# RH024_1.net
KiCad netlist of a schematic drawn in EAGLE
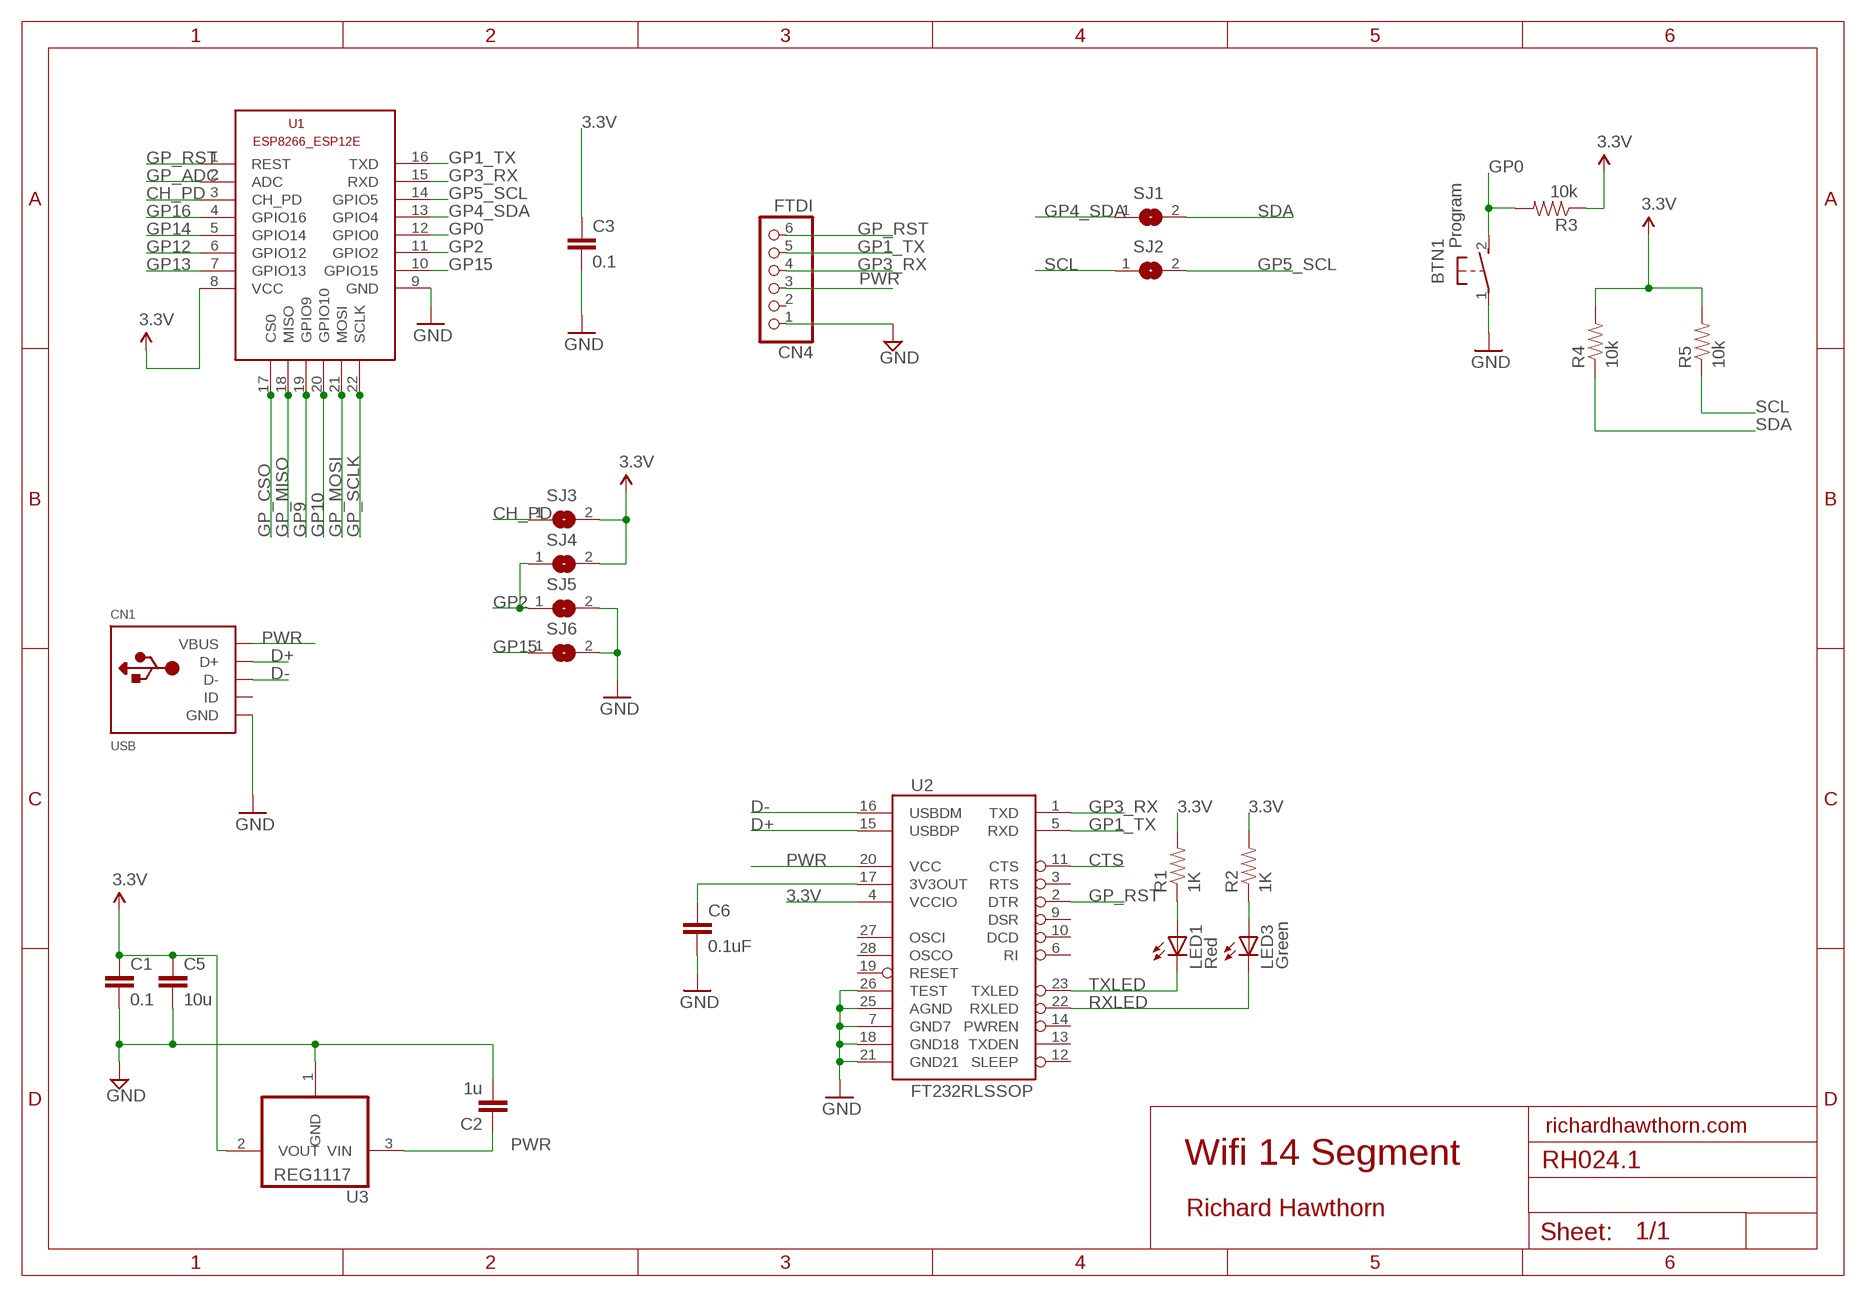
[diagram p0: schematic, sheet 1, part 1 of 2]
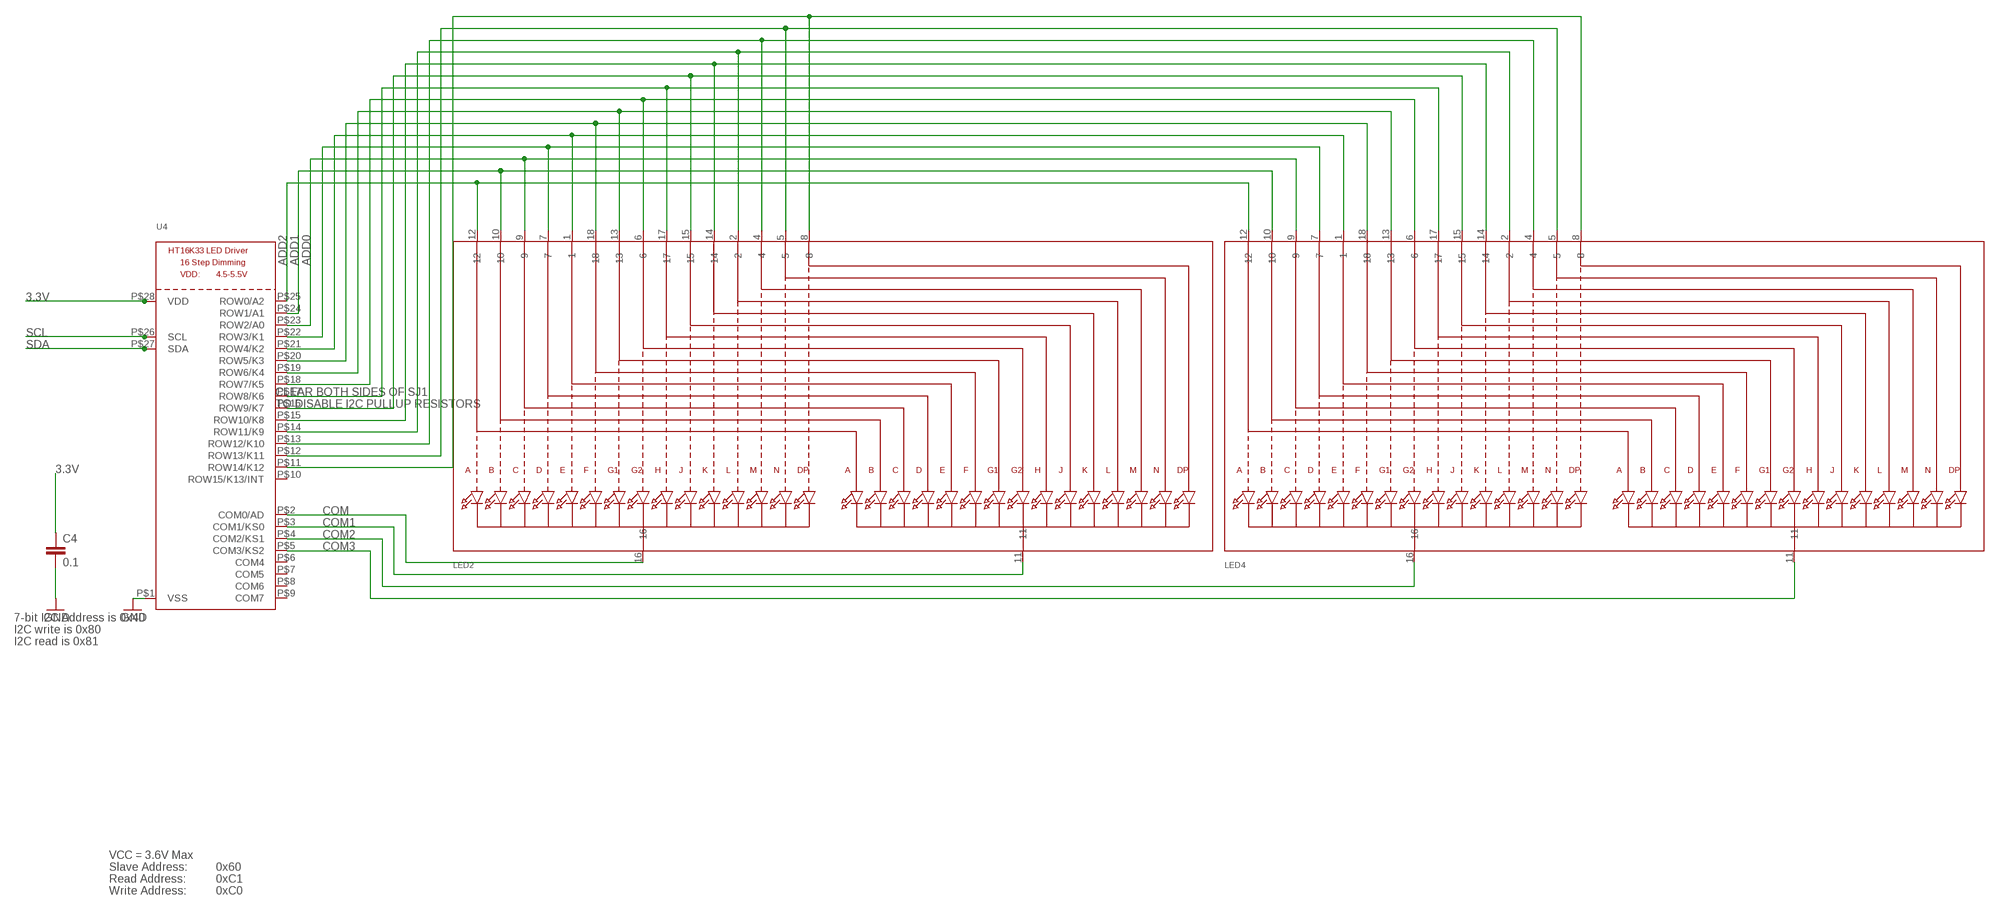
[diagram p1: schematic, sheet 1, part 2 of 2]

(export (version "E")
  (design (tool "Eeschema 10.0.6"))
  (components
    (comp (ref "BTN1")
      (value "Program")
      (footprint "eagle-import:DTS-3")
      (libsource (lib "eagle-import") (part "DTS-3"))
    )
    (comp (ref "C1")
      (value "0.1")
      (footprint "eagle-import:0603-CAP")
      (libsource (lib "eagle-import") (part "CAP0603-CAP"))
    )
    (comp (ref "C2")
      (value "1u")
      (footprint "eagle-import:0603-CAP")
      (libsource (lib "eagle-import") (part "CAP0603-CAP"))
    )
    (comp (ref "C3")
      (value "0.1")
      (footprint "eagle-import:0603-CAP")
      (libsource (lib "eagle-import") (part "CAP0603-CAP"))
    )
    (comp (ref "C4")
      (value "0.1")
      (footprint "eagle-import:0603-CAP")
      (libsource (lib "eagle-import") (part "CAP0603-CAP"))
    )
    (comp (ref "C5")
      (value "10u")
      (footprint "eagle-import:0805-CAP")
      (libsource (lib "eagle-import") (part "CAP0805-CAP"))
    )
    (comp (ref "C6")
      (value "0.1uF")
      (footprint "eagle-import:0402-CAP")
      (libsource (lib "eagle-import") (part "SparkFun_CAP0402-CAP"))
    )
    (comp (ref "CN1")
      (value "USB")
      (footprint "eagle-import:USB-MINIB")
      (libsource (lib "eagle-import") (part "USBMINIB"))
    )
    (comp (ref "CN4")
      (value "FTDI")
      (footprint "eagle-import:1X06")
      (libsource (lib "eagle-import") (part "PINHD-1X6"))
    )
    (comp (ref "LED1")
      (value "Red")
      (footprint "eagle-import:LED-0603")
      (libsource (lib "eagle-import") (part "LED0603"))
    )
    (comp (ref "LED2")
      (value "DISP_SEGMENT_STARBURST_DUAL_COMMONCATHODE")
      (footprint "eagle-import:SEGMENT_STARTBUST_DUAL_KWA-541CBB")
      (libsource (lib "eagle-import") (part "DISP_SEGMENT_STARBURST_DUAL_COMMONCATHODE"))
    )
    (comp (ref "LED3")
      (value "Green")
      (footprint "eagle-import:LED-0603")
      (libsource (lib "eagle-import") (part "LED0603"))
    )
    (comp (ref "LED4")
      (value "DISP_SEGMENT_STARBURST_DUAL_COMMONCATHODE")
      (footprint "eagle-import:SEGMENT_STARTBUST_DUAL_KWA-541CBB")
      (libsource (lib "eagle-import") (part "DISP_SEGMENT_STARBURST_DUAL_COMMONCATHODE"))
    )
    (comp (ref "R1")
      (value "1K")
      (footprint "eagle-import:0402-RES")
      (libsource (lib "eagle-import") (part "RESISTOR0402-RES"))
    )
    (comp (ref "R2")
      (value "1K")
      (footprint "eagle-import:0402-RES")
      (libsource (lib "eagle-import") (part "RESISTOR0402-RES"))
    )
    (comp (ref "R3")
      (value "10k")
      (footprint "eagle-import:0805")
      (libsource (lib "eagle-import") (part "RESISTOR0805-RES"))
    )
    (comp (ref "R4")
      (value "10k")
      (footprint "eagle-import:0805")
      (libsource (lib "eagle-import") (part "RESISTOR0805-RES"))
    )
    (comp (ref "R5")
      (value "10k")
      (footprint "eagle-import:0805")
      (libsource (lib "eagle-import") (part "RESISTOR0805-RES"))
    )
    (comp (ref "SJ1") (value "SJ") (footprint "eagle-import:SJ") (libsource (lib "eagle-import") (part "SJ")))
    (comp (ref "SJ2") (value "SJ") (footprint "eagle-import:SJ") (libsource (lib "eagle-import") (part "SJ")))
    (comp (ref "SJ3") (value "SJ") (footprint "eagle-import:SJ") (libsource (lib "eagle-import") (part "SJ")))
    (comp (ref "SJ4") (value "SJ") (footprint "eagle-import:SJ") (libsource (lib "eagle-import") (part "SJ")))
    (comp (ref "SJ5") (value "SJ") (footprint "eagle-import:SJ") (libsource (lib "eagle-import") (part "SJ")))
    (comp (ref "SJ6") (value "SJ") (footprint "eagle-import:SJ") (libsource (lib "eagle-import") (part "SJ")))
    (comp (ref "U1")
      (value "ESP8266-12EESP8266-ESP12E")
      (footprint "eagle-import:ESP8266-ESP12E")
      (libsource (lib "eagle-import") (part "ESP8266-12EESP8266-ESP12E"))
    )
    (comp (ref "U2")
      (value "FT232RLSSOP")
      (footprint "eagle-import:SSOP28DB")
      (libsource (lib "eagle-import") (part "FT232RLSSOP"))
    )
    (comp (ref "U3")
      (value "REG1117")
      (footprint "eagle-import:SOT223")
      (libsource (lib "eagle-import") (part "REG1117"))
    )
    (comp (ref "U4")
      (value "HT16K33_SOP28")
      (footprint "eagle-import:SOP28_300MIL")
      (libsource (lib "eagle-import") (part "HT16K33_SOP28"))
    )
  )
  (nets
    (net (code "1") (name "/ADD0") (class "Default")
      (node (ref "LED2") (pin "9") (pinfunction "9_9") (pintype "bidirectional"))
      (node (ref "LED4") (pin "9") (pinfunction "9_9") (pintype "bidirectional"))
      (node (ref "U4") (pin "P$23") (pinfunction "ROW2/A0_P$23") (pintype "bidirectional"))
    )
    (net (code "2") (name "/ADD1") (class "Default")
      (node (ref "LED2") (pin "10") (pinfunction "10_10") (pintype "bidirectional"))
      (node (ref "LED4") (pin "10") (pinfunction "10_10") (pintype "bidirectional"))
      (node (ref "U4") (pin "P$24") (pinfunction "ROW1/A1_P$24") (pintype "bidirectional"))
    )
    (net (code "3") (name "/ADD2") (class "Default")
      (node (ref "LED2") (pin "12") (pinfunction "12_12") (pintype "bidirectional"))
      (node (ref "LED4") (pin "12") (pinfunction "12_12") (pintype "bidirectional"))
      (node (ref "U4") (pin "P$25") (pinfunction "ROW0/A2_P$25") (pintype "bidirectional"))
    )
    (net (code "4") (name "/CH_PD") (class "Default")
      (node (ref "SJ3") (pin "1") (pinfunction "1_1") (pintype "passive"))
      (node (ref "U1") (pin "3") (pinfunction "CH_PD_3") (pintype "bidirectional"))
    )
    (net (code "5") (name "/COM") (class "Default")
      (node (ref "LED2") (pin "16") (pinfunction "16_16") (pintype "bidirectional"))
      (node (ref "U4") (pin "P$2") (pinfunction "COM0/AD_P$2") (pintype "bidirectional"))
    )
    (net (code "6") (name "/COM1") (class "Default")
      (node (ref "LED2") (pin "11") (pinfunction "11_11") (pintype "bidirectional"))
      (node (ref "U4") (pin "P$3") (pinfunction "COM1/KS0_P$3") (pintype "bidirectional"))
    )
    (net (code "7") (name "/COM2") (class "Default")
      (node (ref "LED4") (pin "16") (pinfunction "16_16") (pintype "bidirectional"))
      (node (ref "U4") (pin "P$4") (pinfunction "COM2/KS1_P$4") (pintype "bidirectional"))
    )
    (net (code "8") (name "/COM3") (class "Default")
      (node (ref "LED4") (pin "11") (pinfunction "11_11") (pintype "bidirectional"))
      (node (ref "U4") (pin "P$5") (pinfunction "COM3/KS2_P$5") (pintype "bidirectional"))
    )
    (net (code "9") (name "/CTS") (class "Default")
      (node (ref "U2") (pin "11") (pinfunction "CTS_11") (pintype "input"))
    )
    (net (code "10") (name "/D+") (class "Default")
      (node (ref "CN1") (pin "D+") (pinfunction "D+_D+") (pintype "bidirectional"))
      (node (ref "U2") (pin "15") (pinfunction "USBDP_15") (pintype "bidirectional"))
    )
    (net (code "11") (name "/D-") (class "Default")
      (node (ref "CN1") (pin "D-") (pinfunction "D-_D-") (pintype "bidirectional"))
      (node (ref "U2") (pin "16") (pinfunction "USBDM_16") (pintype "bidirectional"))
    )
    (net (code "12") (name "/GP0") (class "Default")
      (node (ref "BTN1") (pin "2") (pinfunction "2_2") (pintype "passive"))
      (node (ref "R3") (pin "2") (pinfunction "2_2") (pintype "passive"))
      (node (ref "U1") (pin "12") (pinfunction "GPIO0_12") (pintype "bidirectional"))
    )
    (net (code "13") (name "/GP1_TX") (class "Default")
      (node (ref "CN4") (pin "5") (pinfunction "5_5") (pintype "passive"))
      (node (ref "U1") (pin "16") (pinfunction "TXD_16") (pintype "bidirectional"))
      (node (ref "U2") (pin "5") (pinfunction "RXD_5") (pintype "input"))
    )
    (net (code "14") (name "/GP2") (class "Default")
      (node (ref "SJ4") (pin "1") (pinfunction "1_1") (pintype "passive"))
      (node (ref "SJ5") (pin "1") (pinfunction "1_1") (pintype "passive"))
      (node (ref "U1") (pin "11") (pinfunction "GPIO2_11") (pintype "bidirectional"))
    )
    (net (code "15") (name "/GP3_RX") (class "Default")
      (node (ref "CN4") (pin "4") (pinfunction "4_4") (pintype "passive"))
      (node (ref "U1") (pin "15") (pinfunction "RXD_15") (pintype "bidirectional"))
      (node (ref "U2") (pin "1") (pinfunction "TXD_1") (pintype "output"))
    )
    (net (code "16") (name "/GP4_SDA") (class "Default")
      (node (ref "SJ1") (pin "1") (pinfunction "1_1") (pintype "passive"))
      (node (ref "U1") (pin "13") (pinfunction "GPIO4_13") (pintype "bidirectional"))
    )
    (net (code "17") (name "/GP5_SCL") (class "Default")
      (node (ref "SJ2") (pin "2") (pinfunction "2_2") (pintype "passive"))
      (node (ref "U1") (pin "14") (pinfunction "GPIO5_14") (pintype "bidirectional"))
    )
    (net (code "18") (name "/GP9") (class "Default")
      (node (ref "U1") (pin "19") (pinfunction "GPIO9_19") (pintype "bidirectional"))
    )
    (net (code "19") (name "/GP10") (class "Default")
      (node (ref "U1") (pin "20") (pinfunction "GPIO10_20") (pintype "bidirectional"))
    )
    (net (code "20") (name "/GP12") (class "Default")
      (node (ref "U1") (pin "6") (pinfunction "GPIO12_6") (pintype "bidirectional"))
    )
    (net (code "21") (name "/GP13") (class "Default")
      (node (ref "U1") (pin "7") (pinfunction "GPIO13_7") (pintype "bidirectional"))
    )
    (net (code "22") (name "/GP14") (class "Default")
      (node (ref "U1") (pin "5") (pinfunction "GPIO14_5") (pintype "bidirectional"))
    )
    (net (code "23") (name "/GP15") (class "Default")
      (node (ref "SJ6") (pin "1") (pinfunction "1_1") (pintype "passive"))
      (node (ref "U1") (pin "10") (pinfunction "GPIO15_10") (pintype "bidirectional"))
    )
    (net (code "24") (name "/GP16") (class "Default")
      (node (ref "U1") (pin "4") (pinfunction "GPIO16_4") (pintype "bidirectional"))
    )
    (net (code "25") (name "/GP_ADC") (class "Default")
      (node (ref "U1") (pin "2") (pinfunction "ADC_2") (pintype "bidirectional"))
    )
    (net (code "26") (name "/GP_CSO") (class "Default")
      (node (ref "U1") (pin "17") (pinfunction "CS0_17") (pintype "bidirectional"))
    )
    (net (code "27") (name "/GP_MISO") (class "Default")
      (node (ref "U1") (pin "18") (pinfunction "MISO_18") (pintype "bidirectional"))
    )
    (net (code "28") (name "/GP_MOSI") (class "Default")
      (node (ref "U1") (pin "21") (pinfunction "MOSI_21") (pintype "bidirectional"))
    )
    (net (code "29") (name "/GP_RST") (class "Default")
      (node (ref "CN4") (pin "6") (pinfunction "6_6") (pintype "passive"))
      (node (ref "U1") (pin "1") (pinfunction "REST_1") (pintype "bidirectional"))
      (node (ref "U2") (pin "2") (pinfunction "DTR_2") (pintype "output"))
    )
    (net (code "30") (name "/GP_SCLK") (class "Default")
      (node (ref "U1") (pin "22") (pinfunction "SCLK_22") (pintype "bidirectional"))
    )
    (net (code "31") (name "/PWR") (class "Default")
      (node (ref "C2") (pin "1") (pinfunction "1_1") (pintype "passive"))
      (node (ref "CN1") (pin "VBUS") (pinfunction "VBUS_VBUS") (pintype "power_in"))
      (node (ref "CN4") (pin "3") (pinfunction "3_3") (pintype "passive"))
      (node (ref "U2") (pin "20") (pinfunction "VCC_20") (pintype "power_in"))
      (node (ref "U3") (pin "3") (pinfunction "VIN_3") (pintype "input"))
    )
    (net (code "32") (name "/RXLED") (class "Default")
      (node (ref "LED3") (pin "C") (pinfunction "C_C") (pintype "passive"))
      (node (ref "U2") (pin "22") (pinfunction "RXLED_22") (pintype "input"))
    )
    (net (code "33") (name "/SCL") (class "Default")
      (node (ref "R5") (pin "1") (pinfunction "1_1") (pintype "passive"))
      (node (ref "SJ2") (pin "1") (pinfunction "1_1") (pintype "passive"))
      (node (ref "U4") (pin "P$26") (pinfunction "SCL_P$26") (pintype "bidirectional"))
    )
    (net (code "34") (name "/SDA") (class "Default")
      (node (ref "R4") (pin "1") (pinfunction "1_1") (pintype "passive"))
      (node (ref "SJ1") (pin "2") (pinfunction "2_2") (pintype "passive"))
      (node (ref "U4") (pin "P$27") (pinfunction "SDA_P$27") (pintype "bidirectional"))
    )
    (net (code "35") (name "/TXLED") (class "Default")
      (node (ref "LED1") (pin "C") (pinfunction "C_C") (pintype "passive"))
      (node (ref "U2") (pin "23") (pinfunction "TXLED_23") (pintype "input"))
    )
    (net (code "36") (name "3.3V") (class "Default")
      (node (ref "C1") (pin "1") (pinfunction "1_1") (pintype "passive"))
      (node (ref "C3") (pin "1") (pinfunction "1_1") (pintype "passive"))
      (node (ref "C4") (pin "1") (pinfunction "1_1") (pintype "passive"))
      (node (ref "C5") (pin "1") (pinfunction "1_1") (pintype "passive"))
      (node (ref "R1") (pin "2") (pinfunction "2_2") (pintype "passive"))
      (node (ref "R2") (pin "2") (pinfunction "2_2") (pintype "passive"))
      (node (ref "R3") (pin "1") (pinfunction "1_1") (pintype "passive"))
      (node (ref "R4") (pin "2") (pinfunction "2_2") (pintype "passive"))
      (node (ref "R5") (pin "2") (pinfunction "2_2") (pintype "passive"))
      (node (ref "SJ3") (pin "2") (pinfunction "2_2") (pintype "passive"))
      (node (ref "SJ4") (pin "2") (pinfunction "2_2") (pintype "passive"))
      (node (ref "U1") (pin "8") (pinfunction "VCC_8") (pintype "bidirectional"))
      (node (ref "U2") (pin "4") (pinfunction "VCCIO_4") (pintype "power_in"))
      (node (ref "U3") (pin "2") (pinfunction "VOUT_2") (pintype "output"))
      (node (ref "U4") (pin "P$28") (pinfunction "VDD_P$28") (pintype "bidirectional"))
    )
    (net (code "37") (name "GND") (class "Default")
      (node (ref "BTN1") (pin "1") (pinfunction "1_1") (pintype "passive"))
      (node (ref "C1") (pin "2") (pinfunction "2_2") (pintype "passive"))
      (node (ref "C2") (pin "2") (pinfunction "2_2") (pintype "passive"))
      (node (ref "C3") (pin "2") (pinfunction "2_2") (pintype "passive"))
      (node (ref "C4") (pin "2") (pinfunction "2_2") (pintype "passive"))
      (node (ref "C5") (pin "2") (pinfunction "2_2") (pintype "passive"))
      (node (ref "C6") (pin "2") (pinfunction "2_2") (pintype "passive"))
      (node (ref "CN1") (pin "GND") (pinfunction "GND_GND") (pintype "power_in"))
      (node (ref "CN4") (pin "1") (pinfunction "1_1") (pintype "passive"))
      (node (ref "SJ5") (pin "2") (pinfunction "2_2") (pintype "passive"))
      (node (ref "SJ6") (pin "2") (pinfunction "2_2") (pintype "passive"))
      (node (ref "U1") (pin "9") (pinfunction "GND_9") (pintype "bidirectional"))
      (node (ref "U2") (pin "18") (pinfunction "GND18_18") (pintype "power_in"))
      (node (ref "U2") (pin "21") (pinfunction "GND21_21") (pintype "power_in"))
      (node (ref "U2") (pin "25") (pinfunction "AGND_25") (pintype "power_in"))
      (node (ref "U2") (pin "26") (pinfunction "TEST_26") (pintype "input"))
      (node (ref "U2") (pin "7") (pinfunction "GND7_7") (pintype "power_in"))
      (node (ref "U3") (pin "1") (pinfunction "GND_1") (pintype "power_in"))
      (node (ref "U4") (pin "P$1") (pinfunction "VSS_P$1") (pintype "bidirectional"))
    )
    (net (code "38") (name "Net-(LED1-PadA)") (class "Default")
      (node (ref "LED1") (pin "A") (pinfunction "A_A") (pintype "passive"))
      (node (ref "R1") (pin "1") (pinfunction "1_1") (pintype "passive"))
    )
    (net (code "39") (name "Net-(LED3-PadA)") (class "Default")
      (node (ref "LED3") (pin "A") (pinfunction "A_A") (pintype "passive"))
      (node (ref "R2") (pin "1") (pinfunction "1_1") (pintype "passive"))
    )
    (net (code "40") (name "Net-(U2-3V3OUT)") (class "Default")
      (node (ref "C6") (pin "1") (pinfunction "1_1") (pintype "passive"))
      (node (ref "U2") (pin "17") (pinfunction "3V3OUT_17") (pintype "output"))
    )
    (net (code "41") (name "Net-(U4-ROW3{slash}K1)") (class "Default")
      (node (ref "LED2") (pin "7") (pinfunction "7_7") (pintype "bidirectional"))
      (node (ref "LED4") (pin "7") (pinfunction "7_7") (pintype "bidirectional"))
      (node (ref "U4") (pin "P$22") (pinfunction "ROW3/K1_P$22") (pintype "bidirectional"))
    )
    (net (code "42") (name "Net-(U4-ROW4{slash}K2)") (class "Default")
      (node (ref "LED2") (pin "1") (pinfunction "1_1") (pintype "bidirectional"))
      (node (ref "LED4") (pin "1") (pinfunction "1_1") (pintype "bidirectional"))
      (node (ref "U4") (pin "P$21") (pinfunction "ROW4/K2_P$21") (pintype "bidirectional"))
    )
    (net (code "43") (name "Net-(U4-ROW5{slash}K3)") (class "Default")
      (node (ref "LED2") (pin "18") (pinfunction "18_18") (pintype "bidirectional"))
      (node (ref "LED4") (pin "18") (pinfunction "18_18") (pintype "bidirectional"))
      (node (ref "U4") (pin "P$20") (pinfunction "ROW5/K3_P$20") (pintype "bidirectional"))
    )
    (net (code "44") (name "Net-(U4-ROW6{slash}K4)") (class "Default")
      (node (ref "LED2") (pin "13") (pinfunction "13_13") (pintype "bidirectional"))
      (node (ref "LED4") (pin "13") (pinfunction "13_13") (pintype "bidirectional"))
      (node (ref "U4") (pin "P$19") (pinfunction "ROW6/K4_P$19") (pintype "bidirectional"))
    )
    (net (code "45") (name "Net-(U4-ROW7{slash}K5)") (class "Default")
      (node (ref "LED2") (pin "6") (pinfunction "6_6") (pintype "bidirectional"))
      (node (ref "LED4") (pin "6") (pinfunction "6_6") (pintype "bidirectional"))
      (node (ref "U4") (pin "P$18") (pinfunction "ROW7/K5_P$18") (pintype "bidirectional"))
    )
    (net (code "46") (name "Net-(U4-ROW8{slash}K6)") (class "Default")
      (node (ref "LED2") (pin "17") (pinfunction "17_17") (pintype "bidirectional"))
      (node (ref "LED4") (pin "17") (pinfunction "17_17") (pintype "bidirectional"))
      (node (ref "U4") (pin "P$17") (pinfunction "ROW8/K6_P$17") (pintype "bidirectional"))
    )
    (net (code "47") (name "Net-(U4-ROW9{slash}K7)") (class "Default")
      (node (ref "LED2") (pin "15") (pinfunction "15_15") (pintype "bidirectional"))
      (node (ref "LED4") (pin "15") (pinfunction "15_15") (pintype "bidirectional"))
      (node (ref "U4") (pin "P$16") (pinfunction "ROW9/K7_P$16") (pintype "bidirectional"))
    )
    (net (code "48") (name "Net-(U4-ROW10{slash}K8)") (class "Default")
      (node (ref "LED2") (pin "14") (pinfunction "14_14") (pintype "bidirectional"))
      (node (ref "LED4") (pin "14") (pinfunction "14_14") (pintype "bidirectional"))
      (node (ref "U4") (pin "P$15") (pinfunction "ROW10/K8_P$15") (pintype "bidirectional"))
    )
    (net (code "49") (name "Net-(U4-ROW11{slash}K9)") (class "Default")
      (node (ref "LED2") (pin "2") (pinfunction "2_2") (pintype "bidirectional"))
      (node (ref "LED4") (pin "2") (pinfunction "2_2") (pintype "bidirectional"))
      (node (ref "U4") (pin "P$14") (pinfunction "ROW11/K9_P$14") (pintype "bidirectional"))
    )
    (net (code "50") (name "Net-(U4-ROW12{slash}K10)") (class "Default")
      (node (ref "LED2") (pin "4") (pinfunction "4_4") (pintype "bidirectional"))
      (node (ref "LED4") (pin "4") (pinfunction "4_4") (pintype "bidirectional"))
      (node (ref "U4") (pin "P$13") (pinfunction "ROW12/K10_P$13") (pintype "bidirectional"))
    )
    (net (code "51") (name "Net-(U4-ROW13{slash}K11)") (class "Default")
      (node (ref "LED2") (pin "5") (pinfunction "5_5") (pintype "bidirectional"))
      (node (ref "LED4") (pin "5") (pinfunction "5_5") (pintype "bidirectional"))
      (node (ref "U4") (pin "P$12") (pinfunction "ROW13/K11_P$12") (pintype "bidirectional"))
    )
    (net (code "52") (name "Net-(U4-ROW14{slash}K12)") (class "Default")
      (node (ref "LED2") (pin "8") (pinfunction "8_8") (pintype "bidirectional"))
      (node (ref "LED4") (pin "8") (pinfunction "8_8") (pintype "bidirectional"))
      (node (ref "U4") (pin "P$11") (pinfunction "ROW14/K12_P$11") (pintype "bidirectional"))
    )
    (net (code "53") (name "unconnected-(CN1-PadID)") (class "Default")
      (node (ref "CN1") (pin "ID") (pinfunction "ID_ID") (pintype "bidirectional"))
    )
    (net (code "54") (name "unconnected-(CN4-Pad2)") (class "Default")
      (node (ref "CN4") (pin "2") (pinfunction "2_2") (pintype "passive"))
    )
    (net (code "55") (name "unconnected-(U2-DCD-Pad10)") (class "Default")
      (node (ref "U2") (pin "10") (pinfunction "DCD_10") (pintype "input"))
    )
    (net (code "56") (name "unconnected-(U2-DSR-Pad9)") (class "Default")
      (node (ref "U2") (pin "9") (pinfunction "DSR_9") (pintype "input"))
    )
    (net (code "57") (name "unconnected-(U2-OSCI-Pad27)") (class "Default")
      (node (ref "U2") (pin "27") (pinfunction "OSCI_27") (pintype "input"))
    )
    (net (code "58") (name "unconnected-(U2-OSCO-Pad28)") (class "Default")
      (node (ref "U2") (pin "28") (pinfunction "OSCO_28") (pintype "output"))
    )
    (net (code "59") (name "unconnected-(U2-PWREN-Pad14)") (class "Default")
      (node (ref "U2") (pin "14") (pinfunction "PWREN_14") (pintype "input"))
    )
    (net (code "60") (name "unconnected-(U2-RESET-Pad19)") (class "Default")
      (node (ref "U2") (pin "19") (pinfunction "RESET_19") (pintype "input"))
    )
    (net (code "61") (name "unconnected-(U2-RI-Pad6)") (class "Default")
      (node (ref "U2") (pin "6") (pinfunction "RI_6") (pintype "input"))
    )
    (net (code "62") (name "unconnected-(U2-RTS-Pad3)") (class "Default")
      (node (ref "U2") (pin "3") (pinfunction "RTS_3") (pintype "output"))
    )
    (net (code "63") (name "unconnected-(U2-SLEEP-Pad12)") (class "Default")
      (node (ref "U2") (pin "12") (pinfunction "SLEEP_12") (pintype "input"))
    )
    (net (code "64") (name "unconnected-(U2-TXDEN-Pad13)") (class "Default")
      (node (ref "U2") (pin "13") (pinfunction "TXDEN_13") (pintype "input"))
    )
    (net (code "65") (name "unconnected-(U4-COM4-PadP$6)") (class "Default")
      (node (ref "U4") (pin "P$6") (pinfunction "COM4_P$6") (pintype "bidirectional"))
    )
    (net (code "66") (name "unconnected-(U4-COM5-PadP$7)") (class "Default")
      (node (ref "U4") (pin "P$7") (pinfunction "COM5_P$7") (pintype "bidirectional"))
    )
    (net (code "67") (name "unconnected-(U4-COM6-PadP$8)") (class "Default")
      (node (ref "U4") (pin "P$8") (pinfunction "COM6_P$8") (pintype "bidirectional"))
    )
    (net (code "68") (name "unconnected-(U4-COM7-PadP$9)") (class "Default")
      (node (ref "U4") (pin "P$9") (pinfunction "COM7_P$9") (pintype "bidirectional"))
    )
    (net (code "69") (name "unconnected-(U4-ROW15{slash}K13{slash}INT-PadP$10)") (class "Default")
      (node (ref "U4") (pin "P$10") (pinfunction "ROW15/K13/INT_P$10") (pintype "bidirectional"))
    )
  )
)
